# STM32F030F.net
KiCad netlist of a schematic drawn in Altium Designer
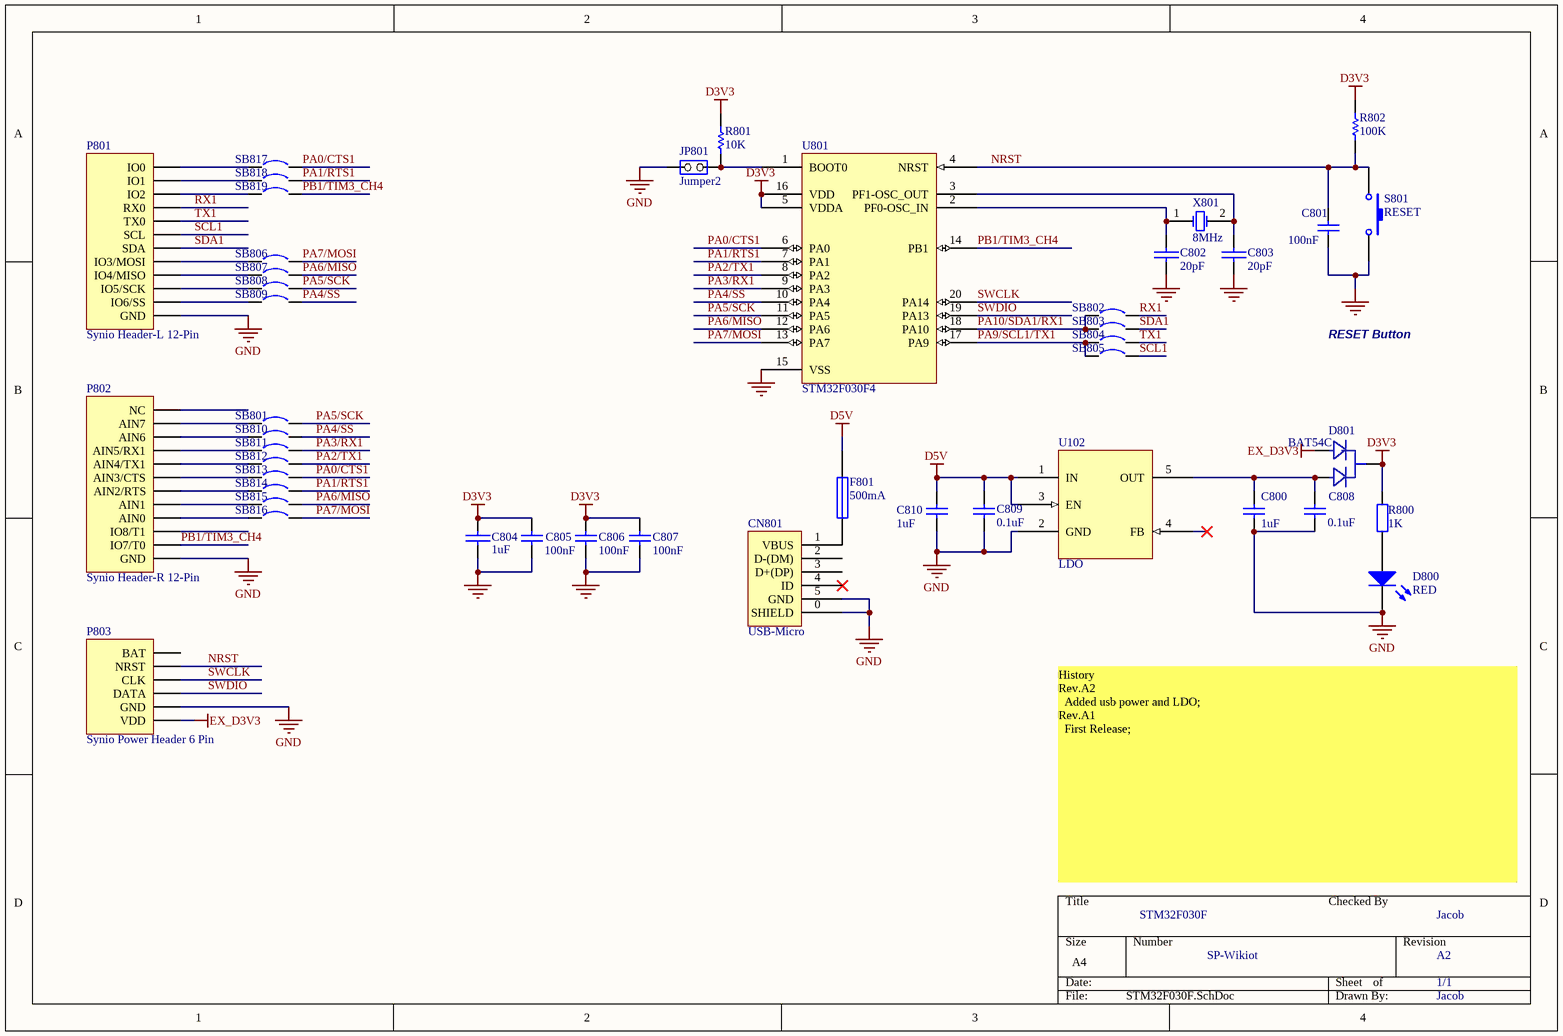
[diagram p0: STM32F030F.SchDoc]

(export (version "E")
  (design (tool "Eeschema 10.0.6"))
  (components
    (comp (ref "C800")
      (value "1uF")
      (footprint "0603M")
      (description "Capacitor")
      (libsource (lib "Studio") (part "Cap"))
    )
    (comp (ref "C801")
      (value "100nF")
      (footprint "0603M")
      (description "Capacitor")
      (fields (field (name "PUBLISHER") "Altium Limited"))
      (libsource (lib "Miscellaneous Devices") (part "CAP"))
    )
    (comp (ref "C802")
      (value "20pF")
      (footprint "0603M")
      (description "Capacitor")
      (libsource (lib "*") (part "CAP"))
    )
    (comp (ref "C803")
      (value "20pF")
      (footprint "0603M")
      (description "Capacitor")
      (libsource (lib "*") (part "CAP"))
    )
    (comp (ref "C804")
      (value "1uF")
      (footprint "0603M")
      (description "Capacitor")
      (libsource (lib "*") (part "CAP"))
    )
    (comp (ref "C805")
      (value "100nF")
      (footprint "0603M")
      (description "Capacitor")
      (fields (field (name "PUBLISHER") "Altium Limited"))
      (libsource (lib "Miscellaneous Devices") (part "Cap"))
    )
    (comp (ref "C806")
      (value "100nF")
      (footprint "0603M")
      (description "Capacitor")
      (fields (field (name "PUBLISHER") "Altium Limited"))
      (libsource (lib "Miscellaneous Devices") (part "Cap"))
    )
    (comp (ref "C807")
      (value "100nF")
      (footprint "0603M")
      (description "Capacitor")
      (fields (field (name "PUBLISHER") "Altium Limited"))
      (libsource (lib "Miscellaneous Devices") (part "Cap"))
    )
    (comp (ref "C808")
      (value "0.1uF")
      (footprint "0603M")
      (description "Capacitor")
      (libsource (lib "Studio") (part "Cap"))
    )
    (comp (ref "C809")
      (value "0.1uF")
      (footprint "0603M")
      (description "Capacitor")
      (libsource (lib "Studio") (part "Cap"))
    )
    (comp (ref "C810")
      (value "1uF")
      (footprint "0603M")
      (description "Capacitor")
      (libsource (lib "Studio") (part "Cap"))
    )
    (comp (ref "CN801")
      (value "USB-Micro")
      (footprint "USB-MICRO-Female-Lite")
      (libsource (lib "Connector") (part "USB-Micro"))
    )
    (comp (ref "D800")
      (value "RED")
      (footprint "0603pn")
      (description "Typical INFRARED GaAs LED")
      (fields (field (name "PUBLISHER") "Altium Limited"))
      (libsource (lib "Miscellaneous Devices") (part "LED0"))
    )
    (comp (ref "D801")
      (value "BAT54C")
      (footprint "BAT54C")
      (description "DOUBLE SHOTTKEY DIODES")
      (libsource (lib "Misc") (part "BAT54C"))
    )
    (comp (ref "F801")
      (value "500mA")
      (footprint "0805")
      (description "Fuse")
      (fields (field (name "PUBLISHER") "Altium Limited"))
      (libsource (lib "Studio") (part "Fuse 1"))
    )
    (comp (ref "JP801") (value "Jumper2") (footprint "SIP2") (libsource (lib "Misc") (part "Jumper2-2")))
    (comp (ref "P801")
      (value "Synio Header-L 12-Pin")
      (footprint "HDR1X12")
      (description "Synio Header-L, 12-Pin")
      (fields (field (name "PUBLISHER") "Altium Limited"))
      (libsource (lib "Connector") (part "Synio Header-L 12-Pin"))
    )
    (comp (ref "P802")
      (value "Synio Header-R 12-Pin")
      (footprint "HDR1X12")
      (description "Synio Header-R, 12-Pin")
      (fields (field (name "PUBLISHER") "Altium Limited"))
      (libsource (lib "Connector") (part "Synio Header-R 12-Pin"))
    )
    (comp (ref "P803")
      (value "Synio Power Header 6 Pin")
      (footprint "HDR1X6/2.54MM")
      (libsource (lib "Connector") (part "Synio Power Header 6 Pin"))
    )
    (comp (ref "R800")
      (value "1K")
      (footprint "0603M")
      (description "Resistor")
      (fields (field (name "PUBLISHER") "Altium Limited"))
      (libsource (lib "Miscellaneous Devices") (part "Res2"))
    )
    (comp (ref "R801")
      (value "10K")
      (footprint "0603M")
      (description "Resistor")
      (fields (field (name "PUBLISHER") "Altium Limited"))
      (libsource (lib "Miscellaneous Devices") (part "res1"))
    )
    (comp (ref "R802")
      (value "100K")
      (footprint "0603M")
      (description "Resistor")
      (fields (field (name "PUBLISHER") "Altium Limited"))
      (libsource (lib "Miscellaneous Devices") (part "res1"))
    )
    (comp (ref "S801")
      (value "RESET")
      (footprint "KEY-2x4-SMD")
      (description "Switch")
      (fields (field (name "PUBLISHER") "Altium Limited"))
      (libsource (lib "Miscellaneous Devices") (part "SW-PB"))
    )
    (comp (ref "SB801")
      (value "Circuit Breaker")
      (footprint "JP2_SMD")
      (fields (field (name "PUBLISHER") "Altium Limited"))
      (libsource (lib "Misc") (part "Circuit Breaker"))
    )
    (comp (ref "SB802")
      (value "Circuit Breaker")
      (footprint "JP2_SMD")
      (fields (field (name "PUBLISHER") "Altium Limited"))
      (libsource (lib "Misc") (part "Circuit Breaker"))
    )
    (comp (ref "SB803")
      (value "Circuit Breaker")
      (footprint "JP2_SMD")
      (fields (field (name "PUBLISHER") "Altium Limited"))
      (libsource (lib "Misc") (part "Circuit Breaker"))
    )
    (comp (ref "SB804")
      (value "Circuit Breaker")
      (footprint "JP2_SMD")
      (fields (field (name "PUBLISHER") "Altium Limited"))
      (libsource (lib "Misc") (part "Circuit Breaker"))
    )
    (comp (ref "SB805")
      (value "Circuit Breaker")
      (footprint "JP2_SMD")
      (fields (field (name "PUBLISHER") "Altium Limited"))
      (libsource (lib "Misc") (part "Circuit Breaker"))
    )
    (comp (ref "SB806")
      (value "Circuit Breaker")
      (footprint "JP2_SMD")
      (fields (field (name "PUBLISHER") "Altium Limited"))
      (libsource (lib "Misc") (part "Circuit Breaker"))
    )
    (comp (ref "SB807")
      (value "Circuit Breaker")
      (footprint "JP2_SMD")
      (fields (field (name "PUBLISHER") "Altium Limited"))
      (libsource (lib "Misc") (part "Circuit Breaker"))
    )
    (comp (ref "SB808")
      (value "Circuit Breaker")
      (footprint "JP2_SMD")
      (fields (field (name "PUBLISHER") "Altium Limited"))
      (libsource (lib "Misc") (part "Circuit Breaker"))
    )
    (comp (ref "SB809")
      (value "Circuit Breaker")
      (footprint "JP2_SMD")
      (fields (field (name "PUBLISHER") "Altium Limited"))
      (libsource (lib "Misc") (part "Circuit Breaker"))
    )
    (comp (ref "SB810")
      (value "Circuit Breaker")
      (footprint "JP2_SMD")
      (fields (field (name "PUBLISHER") "Altium Limited"))
      (libsource (lib "Misc") (part "Circuit Breaker"))
    )
    (comp (ref "SB811")
      (value "Circuit Breaker")
      (footprint "JP2_SMD")
      (fields (field (name "PUBLISHER") "Altium Limited"))
      (libsource (lib "Misc") (part "Circuit Breaker"))
    )
    (comp (ref "SB812")
      (value "Circuit Breaker")
      (footprint "JP2_SMD")
      (fields (field (name "PUBLISHER") "Altium Limited"))
      (libsource (lib "Misc") (part "Circuit Breaker"))
    )
    (comp (ref "SB813")
      (value "Circuit Breaker")
      (footprint "JP2_SMD")
      (fields (field (name "PUBLISHER") "Altium Limited"))
      (libsource (lib "Misc") (part "Circuit Breaker"))
    )
    (comp (ref "SB814")
      (value "Circuit Breaker")
      (footprint "JP2_SMD")
      (fields (field (name "PUBLISHER") "Altium Limited"))
      (libsource (lib "Misc") (part "Circuit Breaker"))
    )
    (comp (ref "SB815")
      (value "Circuit Breaker")
      (footprint "JP2_SMD")
      (fields (field (name "PUBLISHER") "Altium Limited"))
      (libsource (lib "Misc") (part "Circuit Breaker"))
    )
    (comp (ref "SB816")
      (value "Circuit Breaker")
      (footprint "JP2_SMD")
      (fields (field (name "PUBLISHER") "Altium Limited"))
      (libsource (lib "Misc") (part "Circuit Breaker"))
    )
    (comp (ref "SB817")
      (value "Circuit Breaker")
      (footprint "JP2_SMD")
      (fields (field (name "PUBLISHER") "Altium Limited"))
      (libsource (lib "Misc") (part "Circuit Breaker"))
    )
    (comp (ref "SB818")
      (value "Circuit Breaker")
      (footprint "JP2_SMD")
      (fields (field (name "PUBLISHER") "Altium Limited"))
      (libsource (lib "Misc") (part "Circuit Breaker"))
    )
    (comp (ref "SB819")
      (value "Circuit Breaker")
      (footprint "JP2_SMD")
      (fields (field (name "PUBLISHER") "Altium Limited"))
      (libsource (lib "Misc") (part "Circuit Breaker"))
    )
    (comp (ref "U102")
      (value "LDO")
      (footprint "SOT23-5")
      (description "General LDO SOT23-5")
      (libsource (lib "Power") (part "LDO-SOT23-5"))
    )
    (comp (ref "U801")
      (value "STM32F030F4")
      (footprint "TSSOP20")
      (libsource (lib "Processor") (part "STM32F030F4"))
    )
    (comp (ref "X801")
      (value "8MHz")
      (footprint "XTAL_49S")
      (description "Crystal Oscillator")
      (fields (field (name "PUBLISHER") "Altium Limited"))
      (libsource (lib "MCD_TOOLS") (part "XTAL"))
    )
  )
  (nets
    (net (code "1") (name "/NRST") (class "Default")
      (node (ref "C801") (pin "2") (pinfunction "2_2") (pintype "passive"))
      (node (ref "P803") (pin "5") (pinfunction "NRST_5") (pintype "passive"))
      (node (ref "R802") (pin "1") (pinfunction "1_1") (pintype "passive"))
      (node (ref "S801") (pin "2") (pinfunction "2_2") (pintype "passive"))
      (node (ref "U801") (pin "4") (pinfunction "NRST_4") (pintype "input"))
    )
    (net (code "2") (name "/PA0{slash}CTS1") (class "Default")
      (node (ref "SB813") (pin "2") (pinfunction "2_2") (pintype "passive"))
      (node (ref "SB817") (pin "2") (pinfunction "2_2") (pintype "passive"))
      (node (ref "U801") (pin "6") (pinfunction "PA0_6") (pintype "bidirectional"))
    )
    (net (code "3") (name "/PA1{slash}RTS1") (class "Default")
      (node (ref "SB814") (pin "2") (pinfunction "2_2") (pintype "passive"))
      (node (ref "SB818") (pin "2") (pinfunction "2_2") (pintype "passive"))
      (node (ref "U801") (pin "7") (pinfunction "PA1_7") (pintype "bidirectional"))
    )
    (net (code "4") (name "/PA2{slash}TX1") (class "Default")
      (node (ref "SB812") (pin "2") (pinfunction "2_2") (pintype "passive"))
      (node (ref "U801") (pin "8") (pinfunction "PA2_8") (pintype "bidirectional"))
    )
    (net (code "5") (name "/PA3{slash}RX1") (class "Default")
      (node (ref "SB811") (pin "2") (pinfunction "2_2") (pintype "passive"))
      (node (ref "U801") (pin "9") (pinfunction "PA3_9") (pintype "bidirectional"))
    )
    (net (code "6") (name "/PA4{slash}SS") (class "Default")
      (node (ref "SB809") (pin "2") (pinfunction "2_2") (pintype "passive"))
      (node (ref "SB810") (pin "2") (pinfunction "2_2") (pintype "passive"))
      (node (ref "U801") (pin "10") (pinfunction "PA4_10") (pintype "bidirectional"))
    )
    (net (code "7") (name "/PA5{slash}SCK") (class "Default")
      (node (ref "SB801") (pin "2") (pinfunction "2_2") (pintype "passive"))
      (node (ref "SB808") (pin "2") (pinfunction "2_2") (pintype "passive"))
      (node (ref "U801") (pin "11") (pinfunction "PA5_11") (pintype "bidirectional"))
    )
    (net (code "8") (name "/PA6{slash}MISO") (class "Default")
      (node (ref "SB807") (pin "2") (pinfunction "2_2") (pintype "passive"))
      (node (ref "SB815") (pin "2") (pinfunction "2_2") (pintype "passive"))
      (node (ref "U801") (pin "12") (pinfunction "PA6_12") (pintype "bidirectional"))
    )
    (net (code "9") (name "/PA7{slash}MOSI") (class "Default")
      (node (ref "SB806") (pin "2") (pinfunction "2_2") (pintype "passive"))
      (node (ref "SB816") (pin "2") (pinfunction "2_2") (pintype "passive"))
      (node (ref "U801") (pin "13") (pinfunction "PA7_13") (pintype "bidirectional"))
    )
    (net (code "10") (name "/PA9{slash}SCL1{slash}TX1") (class "Default")
      (node (ref "SB804") (pin "1") (pinfunction "1_1") (pintype "passive"))
      (node (ref "SB805") (pin "1") (pinfunction "1_1") (pintype "passive"))
      (node (ref "U801") (pin "17") (pinfunction "PA9_17") (pintype "bidirectional"))
    )
    (net (code "11") (name "/PA10{slash}SDA1{slash}RX1") (class "Default")
      (node (ref "SB802") (pin "1") (pinfunction "1_1") (pintype "passive"))
      (node (ref "SB803") (pin "1") (pinfunction "1_1") (pintype "passive"))
      (node (ref "U801") (pin "18") (pinfunction "PA10_18") (pintype "bidirectional"))
    )
    (net (code "12") (name "/PB1{slash}TIM3_CH4") (class "Default")
      (node (ref "P802") (pin "2") (pinfunction "IO7/T0_2") (pintype "passive"))
      (node (ref "SB819") (pin "2") (pinfunction "2_2") (pintype "passive"))
      (node (ref "U801") (pin "14") (pinfunction "PB1_14") (pintype "bidirectional"))
    )
    (net (code "13") (name "/RX1") (class "Default")
      (node (ref "P801") (pin "9") (pinfunction "RX0_9") (pintype "passive"))
      (node (ref "SB802") (pin "2") (pinfunction "2_2") (pintype "passive"))
    )
    (net (code "14") (name "/SCL1") (class "Default")
      (node (ref "P801") (pin "7") (pinfunction "SCL_7") (pintype "passive"))
      (node (ref "SB805") (pin "2") (pinfunction "2_2") (pintype "passive"))
    )
    (net (code "15") (name "/SDA1") (class "Default")
      (node (ref "P801") (pin "6") (pinfunction "SDA_6") (pintype "passive"))
      (node (ref "SB803") (pin "2") (pinfunction "2_2") (pintype "passive"))
    )
    (net (code "16") (name "/SWCLK") (class "Default")
      (node (ref "P803") (pin "4") (pinfunction "CLK_4") (pintype "passive"))
      (node (ref "U801") (pin "20") (pinfunction "PA14_20") (pintype "bidirectional"))
    )
    (net (code "17") (name "/SWDIO") (class "Default")
      (node (ref "P803") (pin "3") (pinfunction "DATA_3") (pintype "passive"))
      (node (ref "U801") (pin "19") (pinfunction "PA13_19") (pintype "bidirectional"))
    )
    (net (code "18") (name "/TX1") (class "Default")
      (node (ref "P801") (pin "8") (pinfunction "TX0_8") (pintype "passive"))
      (node (ref "SB804") (pin "2") (pinfunction "2_2") (pintype "passive"))
    )
    (net (code "19") (name "D3V3") (class "Default")
      (node (ref "C804") (pin "1") (pinfunction "1_1") (pintype "passive"))
      (node (ref "C805") (pin "1") (pinfunction "1_1") (pintype "passive"))
      (node (ref "C806") (pin "1") (pinfunction "1_1") (pintype "passive"))
      (node (ref "C807") (pin "1") (pinfunction "1_1") (pintype "passive"))
      (node (ref "D801") (pin "3") (pinfunction "3_3") (pintype "passive"))
      (node (ref "R800") (pin "2") (pinfunction "2_2") (pintype "passive"))
      (node (ref "R801") (pin "1") (pinfunction "1_1") (pintype "passive"))
      (node (ref "R802") (pin "2") (pinfunction "2_2") (pintype "passive"))
      (node (ref "U801") (pin "16") (pinfunction "VDD_16") (pintype "power_in"))
      (node (ref "U801") (pin "5") (pinfunction "VDDA_5") (pintype "power_in"))
    )
    (net (code "20") (name "D5V") (class "Default")
      (node (ref "C809") (pin "2") (pinfunction "2_2") (pintype "passive"))
      (node (ref "C810") (pin "2") (pinfunction "2_2") (pintype "passive"))
      (node (ref "F801") (pin "1") (pinfunction "1_1") (pintype "passive"))
      (node (ref "U102") (pin "1") (pinfunction "IN_1") (pintype "power_in"))
      (node (ref "U102") (pin "3") (pinfunction "EN_3") (pintype "input"))
    )
    (net (code "21") (name "EX_D3V3") (class "Default")
      (node (ref "D801") (pin "1") (pintype "passive"))
      (node (ref "P803") (pin "1") (pinfunction "VDD_1") (pintype "passive"))
    )
    (net (code "22") (name "GND") (class "Default")
      (node (ref "C800") (pin "1") (pinfunction "1_1") (pintype "passive"))
      (node (ref "C801") (pin "1") (pinfunction "1_1") (pintype "passive"))
      (node (ref "C802") (pin "2") (pinfunction "2_2") (pintype "passive"))
      (node (ref "C803") (pin "2") (pinfunction "2_2") (pintype "passive"))
      (node (ref "C804") (pin "2") (pinfunction "2_2") (pintype "passive"))
      (node (ref "C805") (pin "2") (pinfunction "2_2") (pintype "passive"))
      (node (ref "C806") (pin "2") (pinfunction "2_2") (pintype "passive"))
      (node (ref "C807") (pin "2") (pinfunction "2_2") (pintype "passive"))
      (node (ref "C808") (pin "1") (pinfunction "1_1") (pintype "passive"))
      (node (ref "C809") (pin "1") (pinfunction "1_1") (pintype "passive"))
      (node (ref "C810") (pin "1") (pinfunction "1_1") (pintype "passive"))
      (node (ref "CN801") (pin "0") (pinfunction "SHIELD_0") (pintype "passive"))
      (node (ref "CN801") (pin "5") (pinfunction "GND_5") (pintype "passive"))
      (node (ref "D800") (pin "2") (pinfunction "K_2") (pintype "passive"))
      (node (ref "JP801") (pin "1") (pinfunction "COMMON_1") (pintype "passive"))
      (node (ref "P801") (pin "1") (pinfunction "GND_1") (pintype "passive"))
      (node (ref "P802") (pin "1") (pinfunction "GND_1") (pintype "passive"))
      (node (ref "P803") (pin "2") (pinfunction "GND_2") (pintype "passive"))
      (node (ref "S801") (pin "1") (pinfunction "1_1") (pintype "passive"))
      (node (ref "U102") (pin "2") (pinfunction "GND_2") (pintype "power_in"))
      (node (ref "U801") (pin "15") (pinfunction "VSS_15") (pintype "power_in"))
    )
    (net (code "23") (name "Net-(CN801-VBUS)") (class "Default")
      (node (ref "CN801") (pin "1") (pinfunction "VBUS_1") (pintype "passive"))
      (node (ref "F801") (pin "2") (pinfunction "2_2") (pintype "passive"))
    )
    (net (code "24") (name "Net-(D800-A)") (class "Default")
      (node (ref "D800") (pin "1") (pinfunction "A_1") (pintype "passive"))
      (node (ref "R800") (pin "1") (pinfunction "1_1") (pintype "passive"))
    )
    (net (code "25") (name "Net-(JP801-NO)") (class "Default")
      (node (ref "JP801") (pin "2") (pinfunction "NO_2") (pintype "passive"))
      (node (ref "R801") (pin "2") (pinfunction "2_2") (pintype "passive"))
      (node (ref "U801") (pin "1") (pinfunction "BOOT0_1") (pintype "passive"))
    )
    (net (code "26") (name "Net-(P801-IO0)") (class "Default")
      (node (ref "P801") (pin "12") (pinfunction "IO0_12") (pintype "passive"))
      (node (ref "SB817") (pin "1") (pinfunction "1_1") (pintype "passive"))
    )
    (net (code "27") (name "Net-(P801-IO1)") (class "Default")
      (node (ref "P801") (pin "11") (pinfunction "IO1_11") (pintype "passive"))
      (node (ref "SB818") (pin "1") (pinfunction "1_1") (pintype "passive"))
    )
    (net (code "28") (name "Net-(P801-IO2)") (class "Default")
      (node (ref "P801") (pin "10") (pinfunction "IO2_10") (pintype "passive"))
      (node (ref "SB819") (pin "1") (pinfunction "1_1") (pintype "passive"))
    )
    (net (code "29") (name "Net-(P801-IO3{slash}MOSI)") (class "Default")
      (node (ref "P801") (pin "5") (pinfunction "IO3/MOSI_5") (pintype "passive"))
      (node (ref "SB806") (pin "1") (pinfunction "1_1") (pintype "passive"))
    )
    (net (code "30") (name "Net-(P801-IO4{slash}MISO)") (class "Default")
      (node (ref "P801") (pin "4") (pinfunction "IO4/MISO_4") (pintype "passive"))
      (node (ref "SB807") (pin "1") (pinfunction "1_1") (pintype "passive"))
    )
    (net (code "31") (name "Net-(P801-IO5{slash}SCK)") (class "Default")
      (node (ref "P801") (pin "3") (pinfunction "IO5/SCK_3") (pintype "passive"))
      (node (ref "SB808") (pin "1") (pinfunction "1_1") (pintype "passive"))
    )
    (net (code "32") (name "Net-(P801-IO6{slash}SS)") (class "Default")
      (node (ref "P801") (pin "2") (pinfunction "IO6/SS_2") (pintype "passive"))
      (node (ref "SB809") (pin "1") (pinfunction "1_1") (pintype "passive"))
    )
    (net (code "33") (name "Net-(P802-AIN0)") (class "Default")
      (node (ref "P802") (pin "4") (pinfunction "AIN0_4") (pintype "passive"))
      (node (ref "SB816") (pin "1") (pinfunction "1_1") (pintype "passive"))
    )
    (net (code "34") (name "Net-(P802-AIN1)") (class "Default")
      (node (ref "P802") (pin "5") (pinfunction "AIN1_5") (pintype "passive"))
      (node (ref "SB815") (pin "1") (pinfunction "1_1") (pintype "passive"))
    )
    (net (code "35") (name "Net-(P802-AIN2{slash}RTS)") (class "Default")
      (node (ref "P802") (pin "6") (pinfunction "AIN2/RTS_6") (pintype "passive"))
      (node (ref "SB814") (pin "1") (pinfunction "1_1") (pintype "passive"))
    )
    (net (code "36") (name "Net-(P802-AIN3{slash}CTS)") (class "Default")
      (node (ref "P802") (pin "7") (pinfunction "AIN3/CTS_7") (pintype "passive"))
      (node (ref "SB813") (pin "1") (pinfunction "1_1") (pintype "passive"))
    )
    (net (code "37") (name "Net-(P802-AIN4{slash}TX1)") (class "Default")
      (node (ref "P802") (pin "8") (pinfunction "AIN4/TX1_8") (pintype "passive"))
      (node (ref "SB812") (pin "1") (pinfunction "1_1") (pintype "passive"))
    )
    (net (code "38") (name "Net-(P802-AIN5{slash}RX1)") (class "Default")
      (node (ref "P802") (pin "9") (pinfunction "AIN5/RX1_9") (pintype "passive"))
      (node (ref "SB811") (pin "1") (pinfunction "1_1") (pintype "passive"))
    )
    (net (code "39") (name "Net-(P802-AIN6)") (class "Default")
      (node (ref "P802") (pin "10") (pinfunction "AIN6_10") (pintype "passive"))
      (node (ref "SB810") (pin "1") (pinfunction "1_1") (pintype "passive"))
    )
    (net (code "40") (name "Net-(P802-AIN7)") (class "Default")
      (node (ref "P802") (pin "11") (pinfunction "AIN7_11") (pintype "passive"))
      (node (ref "SB801") (pin "1") (pinfunction "1_1") (pintype "passive"))
    )
    (net (code "41") (name "Net-(U102-OUT)") (class "Default")
      (node (ref "C800") (pin "2") (pinfunction "2_2") (pintype "passive"))
      (node (ref "C808") (pin "2") (pinfunction "2_2") (pintype "passive"))
      (node (ref "D801") (pin "2") (pintype "passive"))
      (node (ref "U102") (pin "5") (pinfunction "OUT_5") (pintype "power_in"))
    )
    (net (code "42") (name "Net-(U801-PF0-OSC_IN)") (class "Default")
      (node (ref "C802") (pin "1") (pinfunction "1_1") (pintype "passive"))
      (node (ref "U801") (pin "2") (pinfunction "PF0-OSC_IN_2") (pintype "passive"))
      (node (ref "X801") (pin "1") (pinfunction "OSC1_1") (pintype "passive"))
    )
    (net (code "43") (name "Net-(U801-PF1-OSC_OUT)") (class "Default")
      (node (ref "C803") (pin "1") (pinfunction "1_1") (pintype "passive"))
      (node (ref "U801") (pin "3") (pinfunction "PF1-OSC_OUT_3") (pintype "passive"))
      (node (ref "X801") (pin "2") (pinfunction "OSC2_2") (pintype "passive"))
    )
    (net (code "44") (name "unconnected-(CN801-D+(DP)-Pad3)") (class "Default")
      (node (ref "CN801") (pin "3") (pinfunction "D+(DP)_3") (pintype "passive"))
    )
    (net (code "45") (name "unconnected-(CN801-D-(DM)-Pad2)") (class "Default")
      (node (ref "CN801") (pin "2") (pinfunction "D-(DM)_2") (pintype "passive"))
    )
    (net (code "46") (name "unconnected-(CN801-ID-Pad4)") (class "Default")
      (node (ref "CN801") (pin "4") (pinfunction "ID_4") (pintype "passive+no_connect"))
    )
    (net (code "47") (name "unconnected-(P802-IO8{slash}T1-Pad3)") (class "Default")
      (node (ref "P802") (pin "3") (pinfunction "IO8/T1_3") (pintype "passive"))
    )
    (net (code "48") (name "unconnected-(P802-NC-Pad12)") (class "Default")
      (node (ref "P802") (pin "12") (pinfunction "NC_12") (pintype "passive"))
    )
    (net (code "49") (name "unconnected-(P803-BAT-Pad6)") (class "Default")
      (node (ref "P803") (pin "6") (pinfunction "BAT_6") (pintype "passive"))
    )
    (net (code "50") (name "unconnected-(U102-FB-Pad4)") (class "Default")
      (node (ref "U102") (pin "4") (pinfunction "FB_4") (pintype "input+no_connect"))
    )
  )
)
